# Board.net
KiCad netlist of a schematic drawn in Altium Designer
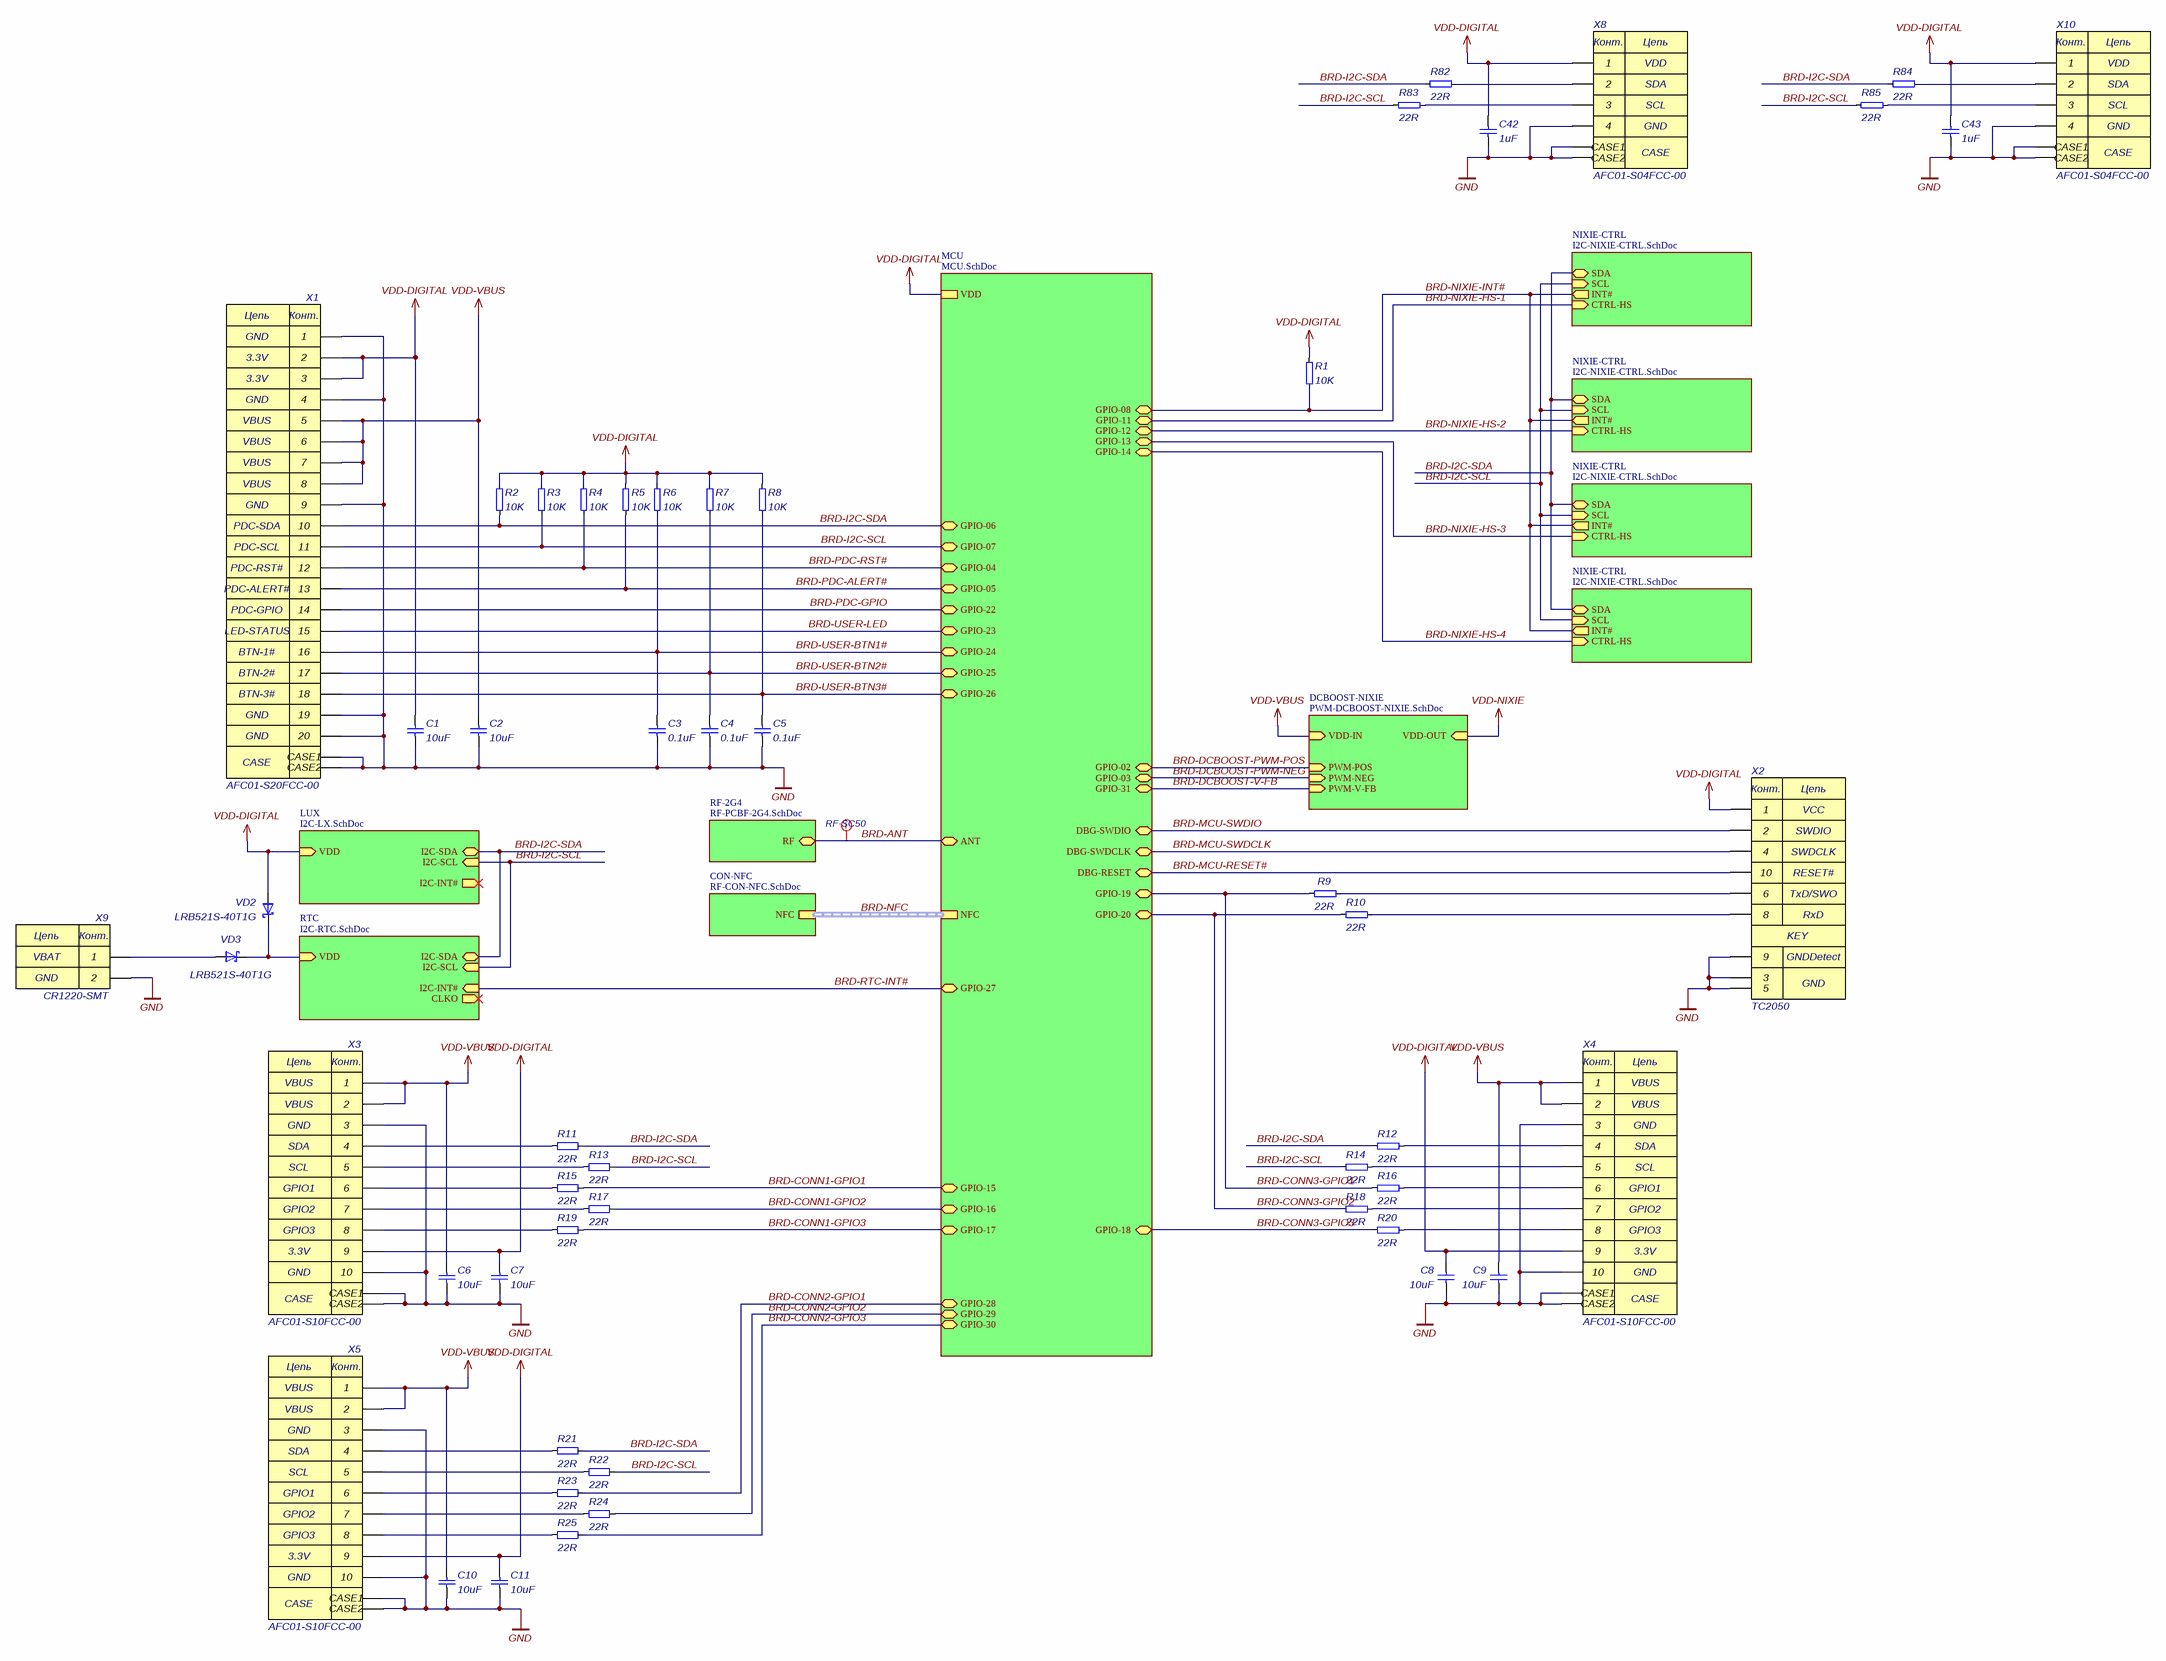
[diagram p0: Board.SchDoc]

(export (version "E")
  (design (tool "Eeschema 10.0.6"))
  (components
    (comp (ref "C1")
      (value "10uF")
      (footprint "C0805")
      (fields
        (field (name "PART NUMBER") "0805-X5R-25V-10uF±10%")
        (field (name "VOLTAGE") "25V")
        (field (name "TOLERANCE") "10%")
      )
      (libsource (lib "ATB") (part "C"))
    )
    (comp (ref "C2")
      (value "10uF")
      (footprint "C0805")
      (fields
        (field (name "PART NUMBER") "0805-X5R-25V-10uF±10%")
        (field (name "VOLTAGE") "25V")
        (field (name "TOLERANCE") "10%")
      )
      (libsource (lib "ATB") (part "C"))
    )
    (comp (ref "C3")
      (value "0.1uF")
      (footprint "C0402")
      (fields
        (field (name "PART NUMBER") "0402-X5R-50V-0.1uF±10%")
        (field (name "VOLTAGE") "50V")
        (field (name "TOLERANCE") "10%")
      )
      (libsource (lib "ATB") (part "C"))
    )
    (comp (ref "C4")
      (value "0.1uF")
      (footprint "C0402")
      (fields
        (field (name "PART NUMBER") "0402-X5R-50V-0.1uF±10%")
        (field (name "VOLTAGE") "50V")
        (field (name "TOLERANCE") "10%")
      )
      (libsource (lib "ATB") (part "C"))
    )
    (comp (ref "C5")
      (value "0.1uF")
      (footprint "C0402")
      (fields
        (field (name "PART NUMBER") "0402-X5R-50V-0.1uF±10%")
        (field (name "VOLTAGE") "50V")
        (field (name "TOLERANCE") "10%")
      )
      (libsource (lib "ATB") (part "C"))
    )
    (comp (ref "C6")
      (value "10uF")
      (footprint "C0805")
      (fields
        (field (name "PART NUMBER") "0805-X5R-25V-10uF±10%")
        (field (name "VOLTAGE") "25V")
        (field (name "TOLERANCE") "10%")
      )
      (libsource (lib "ATB") (part "C"))
    )
    (comp (ref "C7")
      (value "10uF")
      (footprint "C0805")
      (fields
        (field (name "PART NUMBER") "0805-X5R-25V-10uF±10%")
        (field (name "VOLTAGE") "25V")
        (field (name "TOLERANCE") "10%")
      )
      (libsource (lib "ATB") (part "C"))
    )
    (comp (ref "C8")
      (value "10uF")
      (footprint "C0805")
      (fields
        (field (name "PART NUMBER") "0805-X5R-25V-10uF±10%")
        (field (name "VOLTAGE") "25V")
        (field (name "TOLERANCE") "10%")
      )
      (libsource (lib "ATB") (part "C"))
    )
    (comp (ref "C9")
      (value "10uF")
      (footprint "C0805")
      (fields
        (field (name "PART NUMBER") "0805-X5R-25V-10uF±10%")
        (field (name "VOLTAGE") "25V")
        (field (name "TOLERANCE") "10%")
      )
      (libsource (lib "ATB") (part "C"))
    )
    (comp (ref "C10")
      (value "10uF")
      (footprint "C0805")
      (fields
        (field (name "PART NUMBER") "0805-X5R-25V-10uF±10%")
        (field (name "VOLTAGE") "25V")
        (field (name "TOLERANCE") "10%")
      )
      (libsource (lib "ATB") (part "C"))
    )
    (comp (ref "C11")
      (value "10uF")
      (footprint "C0805")
      (fields
        (field (name "PART NUMBER") "0805-X5R-25V-10uF±10%")
        (field (name "VOLTAGE") "25V")
        (field (name "TOLERANCE") "10%")
      )
      (libsource (lib "ATB") (part "C"))
    )
    (comp (ref "C42")
      (value "1uF")
      (footprint "C0402")
      (fields
        (field (name "PART NUMBER") "0402-X5R-10V-01uF±10%")
        (field (name "VOLTAGE") "10V")
        (field (name "TOLERANCE") "10%")
      )
      (libsource (lib "ATB") (part "C"))
    )
    (comp (ref "C43")
      (value "1uF")
      (footprint "C0402")
      (fields
        (field (name "PART NUMBER") "0402-X5R-10V-01uF±10%")
        (field (name "VOLTAGE") "10V")
        (field (name "TOLERANCE") "10%")
      )
      (libsource (lib "ATB") (part "C"))
    )
    (comp (ref "R1")
      (value "10K")
      (footprint "R_0402")
      (fields
        (field (name "PART NUMBER") "0402-0.0625W-10K-100ppm±1%")
        (field (name "TOLERANCE") "1%")
        (field (name "MANUFACTURER") "Yageo")
      )
      (libsource (lib "ATB") (part "R"))
    )
    (comp (ref "R2")
      (value "10K")
      (footprint "R_0402")
      (fields
        (field (name "PART NUMBER") "0402-0.0625W-10K-100ppm±1%")
        (field (name "TOLERANCE") "1%")
        (field (name "MANUFACTURER") "Yageo")
      )
      (libsource (lib "ATB") (part "R"))
    )
    (comp (ref "R3")
      (value "10K")
      (footprint "R_0402")
      (fields
        (field (name "PART NUMBER") "0402-0.0625W-10K-100ppm±1%")
        (field (name "TOLERANCE") "1%")
        (field (name "MANUFACTURER") "Yageo")
      )
      (libsource (lib "ATB") (part "R"))
    )
    (comp (ref "R4")
      (value "10K")
      (footprint "R_0402")
      (fields
        (field (name "PART NUMBER") "0402-0.0625W-10K-100ppm±1%")
        (field (name "TOLERANCE") "1%")
        (field (name "MANUFACTURER") "Yageo")
      )
      (libsource (lib "ATB") (part "R"))
    )
    (comp (ref "R5")
      (value "10K")
      (footprint "R_0402")
      (fields
        (field (name "PART NUMBER") "0402-0.0625W-10K-100ppm±1%")
        (field (name "TOLERANCE") "1%")
        (field (name "MANUFACTURER") "Yageo")
      )
      (libsource (lib "ATB") (part "R"))
    )
    (comp (ref "R6")
      (value "10K")
      (footprint "R_0402")
      (fields
        (field (name "PART NUMBER") "0402-0.0625W-10K-100ppm±1%")
        (field (name "TOLERANCE") "1%")
        (field (name "MANUFACTURER") "Yageo")
      )
      (libsource (lib "ATB") (part "R"))
    )
    (comp (ref "R7")
      (value "10K")
      (footprint "R_0402")
      (fields
        (field (name "PART NUMBER") "0402-0.0625W-10K-100ppm±1%")
        (field (name "TOLERANCE") "1%")
        (field (name "MANUFACTURER") "Yageo")
      )
      (libsource (lib "ATB") (part "R"))
    )
    (comp (ref "R8")
      (value "10K")
      (footprint "R_0402")
      (fields
        (field (name "PART NUMBER") "0402-0.0625W-10K-100ppm±1%")
        (field (name "TOLERANCE") "1%")
        (field (name "MANUFACTURER") "Yageo")
      )
      (libsource (lib "ATB") (part "R"))
    )
    (comp (ref "R9")
      (value "22R")
      (footprint "R_0402")
      (fields
        (field (name "PART NUMBER") "0402-0.0625W-22R-100ppm±1%")
        (field (name "TOLERANCE") "1%")
        (field (name "MANUFACTURER") "Yageo")
      )
      (libsource (lib "ATB") (part "R"))
    )
    (comp (ref "R10")
      (value "22R")
      (footprint "R_0402")
      (fields
        (field (name "PART NUMBER") "0402-0.0625W-22R-100ppm±1%")
        (field (name "TOLERANCE") "1%")
        (field (name "MANUFACTURER") "Yageo")
      )
      (libsource (lib "ATB") (part "R"))
    )
    (comp (ref "R11")
      (value "22R")
      (footprint "R_0402")
      (fields
        (field (name "PART NUMBER") "0402-0.0625W-22R-100ppm±1%")
        (field (name "TOLERANCE") "1%")
        (field (name "MANUFACTURER") "Yageo")
      )
      (libsource (lib "ATB") (part "R"))
    )
    (comp (ref "R12")
      (value "22R")
      (footprint "R_0402")
      (fields
        (field (name "PART NUMBER") "0402-0.0625W-22R-100ppm±1%")
        (field (name "TOLERANCE") "1%")
        (field (name "MANUFACTURER") "Yageo")
      )
      (libsource (lib "ATB") (part "R"))
    )
    (comp (ref "R13")
      (value "22R")
      (footprint "R_0402")
      (fields
        (field (name "PART NUMBER") "0402-0.0625W-22R-100ppm±1%")
        (field (name "TOLERANCE") "1%")
        (field (name "MANUFACTURER") "Yageo")
      )
      (libsource (lib "ATB") (part "R"))
    )
    (comp (ref "R14")
      (value "22R")
      (footprint "R_0402")
      (fields
        (field (name "PART NUMBER") "0402-0.0625W-22R-100ppm±1%")
        (field (name "TOLERANCE") "1%")
        (field (name "MANUFACTURER") "Yageo")
      )
      (libsource (lib "ATB") (part "R"))
    )
    (comp (ref "R15")
      (value "22R")
      (footprint "R_0402")
      (fields
        (field (name "PART NUMBER") "0402-0.0625W-22R-100ppm±1%")
        (field (name "TOLERANCE") "1%")
        (field (name "MANUFACTURER") "Yageo")
      )
      (libsource (lib "ATB") (part "R"))
    )
    (comp (ref "R16")
      (value "22R")
      (footprint "R_0402")
      (fields
        (field (name "PART NUMBER") "0402-0.0625W-22R-100ppm±1%")
        (field (name "TOLERANCE") "1%")
        (field (name "MANUFACTURER") "Yageo")
      )
      (libsource (lib "ATB") (part "R"))
    )
    (comp (ref "R17")
      (value "22R")
      (footprint "R_0402")
      (fields
        (field (name "PART NUMBER") "0402-0.0625W-22R-100ppm±1%")
        (field (name "TOLERANCE") "1%")
        (field (name "MANUFACTURER") "Yageo")
      )
      (libsource (lib "ATB") (part "R"))
    )
    (comp (ref "R18")
      (value "22R")
      (footprint "R_0402")
      (fields
        (field (name "PART NUMBER") "0402-0.0625W-22R-100ppm±1%")
        (field (name "TOLERANCE") "1%")
        (field (name "MANUFACTURER") "Yageo")
      )
      (libsource (lib "ATB") (part "R"))
    )
    (comp (ref "R19")
      (value "22R")
      (footprint "R_0402")
      (fields
        (field (name "PART NUMBER") "0402-0.0625W-22R-100ppm±1%")
        (field (name "TOLERANCE") "1%")
        (field (name "MANUFACTURER") "Yageo")
      )
      (libsource (lib "ATB") (part "R"))
    )
    (comp (ref "R20")
      (value "22R")
      (footprint "R_0402")
      (fields
        (field (name "PART NUMBER") "0402-0.0625W-22R-100ppm±1%")
        (field (name "TOLERANCE") "1%")
        (field (name "MANUFACTURER") "Yageo")
      )
      (libsource (lib "ATB") (part "R"))
    )
    (comp (ref "R21")
      (value "22R")
      (footprint "R_0402")
      (fields
        (field (name "PART NUMBER") "0402-0.0625W-22R-100ppm±1%")
        (field (name "TOLERANCE") "1%")
        (field (name "MANUFACTURER") "Yageo")
      )
      (libsource (lib "ATB") (part "R"))
    )
    (comp (ref "R22")
      (value "22R")
      (footprint "R_0402")
      (fields
        (field (name "PART NUMBER") "0402-0.0625W-22R-100ppm±1%")
        (field (name "TOLERANCE") "1%")
        (field (name "MANUFACTURER") "Yageo")
      )
      (libsource (lib "ATB") (part "R"))
    )
    (comp (ref "R23")
      (value "22R")
      (footprint "R_0402")
      (fields
        (field (name "PART NUMBER") "0402-0.0625W-22R-100ppm±1%")
        (field (name "TOLERANCE") "1%")
        (field (name "MANUFACTURER") "Yageo")
      )
      (libsource (lib "ATB") (part "R"))
    )
    (comp (ref "R24")
      (value "22R")
      (footprint "R_0402")
      (fields
        (field (name "PART NUMBER") "0402-0.0625W-22R-100ppm±1%")
        (field (name "TOLERANCE") "1%")
        (field (name "MANUFACTURER") "Yageo")
      )
      (libsource (lib "ATB") (part "R"))
    )
    (comp (ref "R25")
      (value "22R")
      (footprint "R_0402")
      (fields
        (field (name "PART NUMBER") "0402-0.0625W-22R-100ppm±1%")
        (field (name "TOLERANCE") "1%")
        (field (name "MANUFACTURER") "Yageo")
      )
      (libsource (lib "ATB") (part "R"))
    )
    (comp (ref "R82")
      (value "22R")
      (footprint "R_0402")
      (fields
        (field (name "PART NUMBER") "0402-0.0625W-22R-100ppm±1%")
        (field (name "TOLERANCE") "1%")
        (field (name "MANUFACTURER") "Yageo")
      )
      (libsource (lib "ATB") (part "R"))
    )
    (comp (ref "R83")
      (value "22R")
      (footprint "R_0402")
      (fields
        (field (name "PART NUMBER") "0402-0.0625W-22R-100ppm±1%")
        (field (name "TOLERANCE") "1%")
        (field (name "MANUFACTURER") "Yageo")
      )
      (libsource (lib "ATB") (part "R"))
    )
    (comp (ref "R84")
      (value "22R")
      (footprint "R_0402")
      (fields
        (field (name "PART NUMBER") "0402-0.0625W-22R-100ppm±1%")
        (field (name "TOLERANCE") "1%")
        (field (name "MANUFACTURER") "Yageo")
      )
      (libsource (lib "ATB") (part "R"))
    )
    (comp (ref "R85")
      (value "22R")
      (footprint "R_0402")
      (fields
        (field (name "PART NUMBER") "0402-0.0625W-22R-100ppm±1%")
        (field (name "TOLERANCE") "1%")
        (field (name "MANUFACTURER") "Yageo")
      )
      (libsource (lib "ATB") (part "R"))
    )
    (comp (ref "VD2")
      (value "LRB521S-40T1G")
      (footprint "SOD-523")
      (description "40V 300mV 200mA SOD-523 Schottky Barrier Diode")
      (fields (field (name "MANUFACTURER") "LRC"))
      (libsource (lib "ATB") (part "Shotki"))
    )
    (comp (ref "VD3")
      (value "LRB521S-40T1G")
      (footprint "SOD-523")
      (description "40V 300mV 200mA SOD-523 Schottky Barrier Diode")
      (fields (field (name "MANUFACTURER") "LRC"))
      (libsource (lib "ATB") (part "Shotki"))
    )
    (comp (ref "X1")
      (value "AFC01-S20FCC-00")
      (footprint "505110-2096")
      (description "Clamshell -25℃~+85℃ 20P Bottom Contact Surface Mount，Right Angle 0.5mm FFC/FPC Connector")
      (fields (field (name "MANUFACTURER") "JUSHUO"))
      (libsource (lib "ATB") (part "H20+2xCase"))
    )
    (comp (ref "X2")
      (value "TC2050")
      (footprint "TC2050-IDC-FP")
      (description "TAG Connect 10 pin ARM swd compatilbe with UART")
      (fields (field (name "PART NUMBER") "PCB-TAGC-10PIN-SWD-UART"))
      (libsource (lib "ATB") (part "PCB-TAGC-10PIN-SWD-UART"))
    )
    (comp (ref "X3")
      (value "AFC01-S10FCC-00")
      (footprint "505110-1096")
      (description "Clamshell -25℃~+85℃ 10P Bottom Contact Surface Mount，Right Angle 0.5mm FFC/FPC Connector")
      (fields (field (name "MANUFACTURER") "JUSHUO"))
      (libsource (lib "ATB") (part "H10+2xCase"))
    )
    (comp (ref "X4")
      (value "AFC01-S10FCC-00")
      (footprint "505110-1096")
      (description "Clamshell -25℃~+85℃ 10P Bottom Contact Surface Mount，Right Angle 0.5mm FFC/FPC Connector")
      (fields (field (name "MANUFACTURER") "JUSHUO"))
      (libsource (lib "") (part "H10+2xCase_1"))
    )
    (comp (ref "X5")
      (value "AFC01-S10FCC-00")
      (footprint "505110-1096")
      (description "Clamshell -25℃~+85℃ 10P Bottom Contact Surface Mount，Right Angle 0.5mm FFC/FPC Connector")
      (fields (field (name "MANUFACTURER") "JUSHUO"))
      (libsource (lib "ATB") (part "H10+2xCase"))
    )
    (comp (ref "X8")
      (value "AFC01-S04FCC-00")
      (footprint "505110-0492")
      (description "Clamshell 4P Bottom Contact Surface Mount, Right Angle 0.5mm, FFC/FPC Connector")
      (fields (field (name "MANUFACTURER") "JUSHUO"))
      (libsource (lib "ATB") (part "H4+2xCase"))
    )
    (comp (ref "X9")
      (value "CR1220-SMT")
      (footprint "BAT-HLDR-CR1220-SMT")
      (description "Battery base -25℃~+85℃ CR1220 SMD Battery Connector")
      (fields (field (name "PART NUMBER") "L-KLS5-CR1220-02"))
      (libsource (lib "ATB") (part "H2"))
    )
    (comp (ref "X10")
      (value "AFC01-S04FCC-00")
      (footprint "505110-0492")
      (description "Clamshell 4P Bottom Contact Surface Mount, Right Angle 0.5mm, FFC/FPC Connector")
      (fields (field (name "MANUFACTURER") "JUSHUO"))
      (libsource (lib "ATB") (part "H4+2xCase"))
    )
  )
  (nets
    (net (code "3") (name "/BRD-CONN1-GPIO1") (class "Default")
      (node (ref "R15") (pin "2") (pinfunction "2_2") (pintype "passive"))
    )
    (net (code "4") (name "/BRD-CONN1-GPIO2") (class "Default")
      (node (ref "R17") (pin "2") (pinfunction "2_2") (pintype "passive"))
    )
    (net (code "5") (name "/BRD-CONN1-GPIO3") (class "Default")
      (node (ref "R19") (pin "2") (pinfunction "2_2") (pintype "passive"))
    )
    (net (code "6") (name "/BRD-CONN2-GPIO1") (class "Default")
      (node (ref "R23") (pin "2") (pinfunction "2_2") (pintype "passive"))
    )
    (net (code "7") (name "/BRD-CONN2-GPIO2") (class "Default")
      (node (ref "R24") (pin "2") (pinfunction "2_2") (pintype "passive"))
    )
    (net (code "8") (name "/BRD-CONN2-GPIO3") (class "Default")
      (node (ref "R25") (pin "2") (pinfunction "2_2") (pintype "passive"))
    )
    (net (code "9") (name "/BRD-CONN3-GPIO1") (class "Default")
      (node (ref "R16") (pin "2") (pinfunction "2_2") (pintype "passive"))
      (node (ref "R9") (pin "2") (pinfunction "2_2") (pintype "passive"))
    )
    (net (code "10") (name "/BRD-CONN3-GPIO2") (class "Default")
      (node (ref "R10") (pin "2") (pinfunction "2_2") (pintype "passive"))
      (node (ref "R18") (pin "2") (pinfunction "2_2") (pintype "passive"))
    )
    (net (code "11") (name "/BRD-CONN3-GPIO3") (class "Default")
      (node (ref "R20") (pin "2") (pinfunction "2_2") (pintype "passive"))
    )
    (net (code "15") (name "/BRD-I2C-SCL") (class "Default")
      (node (ref "R13") (pin "2") (pinfunction "2_2") (pintype "passive"))
      (node (ref "R14") (pin "2") (pinfunction "2_2") (pintype "passive"))
      (node (ref "R22") (pin "2") (pinfunction "2_2") (pintype "passive"))
      (node (ref "R3") (pin "2") (pinfunction "2_2") (pintype "passive"))
      (node (ref "R83") (pin "2") (pinfunction "2_2") (pintype "passive"))
      (node (ref "R85") (pin "2") (pinfunction "2_2") (pintype "passive"))
      (node (ref "X1") (pin "11") (pinfunction "11_11") (pintype "passive"))
    )
    (net (code "16") (name "/BRD-I2C-SDA") (class "Default")
      (node (ref "R11") (pin "2") (pinfunction "2_2") (pintype "passive"))
      (node (ref "R12") (pin "2") (pinfunction "2_2") (pintype "passive"))
      (node (ref "R2") (pin "2") (pinfunction "2_2") (pintype "passive"))
      (node (ref "R21") (pin "2") (pinfunction "2_2") (pintype "passive"))
      (node (ref "R82") (pin "2") (pinfunction "2_2") (pintype "passive"))
      (node (ref "R84") (pin "2") (pinfunction "2_2") (pintype "passive"))
      (node (ref "X1") (pin "10") (pinfunction "10_10") (pintype "passive"))
    )
    (net (code "17") (name "/BRD-MCU-RESET#") (class "Default")
      (node (ref "X2") (pin "10") (pinfunction "10_10") (pintype "passive"))
    )
    (net (code "18") (name "/BRD-MCU-SWDCLK") (class "Default")
      (node (ref "X2") (pin "4") (pinfunction "4_4") (pintype "passive"))
    )
    (net (code "19") (name "/BRD-MCU-SWDIO") (class "Default")
      (node (ref "X2") (pin "2") (pinfunction "2_2") (pintype "passive"))
    )
    (net (code "24") (name "/BRD-NIXIE-INT#") (class "Default")
      (node (ref "R1") (pin "2") (pinfunction "2_2") (pintype "passive"))
    )
    (net (code "25") (name "/BRD-PDC-ALERT#") (class "Default")
      (node (ref "R5") (pin "2") (pinfunction "2_2") (pintype "passive"))
      (node (ref "X1") (pin "13") (pinfunction "13_13") (pintype "passive"))
    )
    (net (code "26") (name "/BRD-PDC-GPIO") (class "Default")
      (node (ref "X1") (pin "14") (pinfunction "14_14") (pintype "passive"))
    )
    (net (code "27") (name "/BRD-PDC-RST#") (class "Default")
      (node (ref "R4") (pin "2") (pinfunction "2_2") (pintype "passive"))
      (node (ref "X1") (pin "12") (pinfunction "12_12") (pintype "passive"))
    )
    (net (code "29") (name "/BRD-USER-BTN1#") (class "Default")
      (node (ref "C3") (pin "2") (pinfunction "2_2") (pintype "passive"))
      (node (ref "R6") (pin "2") (pinfunction "2_2") (pintype "passive"))
      (node (ref "X1") (pin "16") (pinfunction "16_16") (pintype "passive"))
    )
    (net (code "30") (name "/BRD-USER-BTN2#") (class "Default")
      (node (ref "C4") (pin "2") (pinfunction "2_2") (pintype "passive"))
      (node (ref "R7") (pin "2") (pinfunction "2_2") (pintype "passive"))
      (node (ref "X1") (pin "17") (pinfunction "17_17") (pintype "passive"))
    )
    (net (code "31") (name "/BRD-USER-BTN3#") (class "Default")
      (node (ref "C5") (pin "2") (pinfunction "2_2") (pintype "passive"))
      (node (ref "R8") (pin "2") (pinfunction "2_2") (pintype "passive"))
      (node (ref "X1") (pin "18") (pinfunction "18_18") (pintype "passive"))
    )
    (net (code "32") (name "/BRD-USER-LED") (class "Default")
      (node (ref "X1") (pin "15") (pinfunction "15_15") (pintype "passive"))
    )
    (net (code "35") (name "/VDD") (class "Default")
      (node (ref "VD2") (pin "1") (pinfunction "K_1") (pintype "passive"))
      (node (ref "VD3") (pin "1") (pinfunction "K_1") (pintype "passive"))
    )
    (net (code "37") (name "GND") (class "Default")
      (node (ref "C1") (pin "2") (pinfunction "2_2") (pintype "passive"))
      (node (ref "C10") (pin "2") (pinfunction "2_2") (pintype "passive"))
      (node (ref "C11") (pin "2") (pinfunction "2_2") (pintype "passive"))
      (node (ref "C2") (pin "2") (pinfunction "2_2") (pintype "passive"))
      (node (ref "C3") (pin "1") (pinfunction "1_1") (pintype "passive"))
      (node (ref "C4") (pin "1") (pinfunction "1_1") (pintype "passive"))
      (node (ref "C42") (pin "1") (pinfunction "1_1") (pintype "passive"))
      (node (ref "C43") (pin "1") (pinfunction "1_1") (pintype "passive"))
      (node (ref "C5") (pin "1") (pinfunction "1_1") (pintype "passive"))
      (node (ref "C6") (pin "2") (pinfunction "2_2") (pintype "passive"))
      (node (ref "C7") (pin "2") (pinfunction "2_2") (pintype "passive"))
      (node (ref "C8") (pin "2") (pinfunction "2_2") (pintype "passive"))
      (node (ref "C9") (pin "2") (pinfunction "2_2") (pintype "passive"))
      (node (ref "X1") (pin "1") (pinfunction "1_1") (pintype "passive"))
      (node (ref "X1") (pin "19") (pinfunction "19_19") (pintype "passive"))
      (node (ref "X1") (pin "20") (pinfunction "20_20") (pintype "passive"))
      (node (ref "X1") (pin "4") (pinfunction "4_4") (pintype "passive"))
      (node (ref "X1") (pin "9") (pinfunction "9_9") (pintype "passive"))
      (node (ref "X1") (pin "CASE1") (pinfunction "CASE1_CASE1") (pintype "passive"))
      (node (ref "X1") (pin "CASE2") (pinfunction "CASE2_CASE2") (pintype "passive"))
      (node (ref "X10") (pin "4") (pinfunction "4_4") (pintype "passive"))
      (node (ref "X10") (pin "CASE1") (pinfunction "CASE1_CASE1") (pintype "passive"))
      (node (ref "X10") (pin "CASE2") (pinfunction "CASE2_CASE2") (pintype "passive"))
      (node (ref "X2") (pin "3") (pinfunction "3_3") (pintype "passive"))
      (node (ref "X2") (pin "5") (pinfunction "5_5") (pintype "passive"))
      (node (ref "X2") (pin "9") (pinfunction "9_9") (pintype "passive"))
      (node (ref "X3") (pin "10") (pinfunction "10_10") (pintype "passive"))
      (node (ref "X3") (pin "3") (pinfunction "3_3") (pintype "passive"))
      (node (ref "X3") (pin "CASE1") (pinfunction "CASE1_CASE1") (pintype "passive"))
      (node (ref "X3") (pin "CASE2") (pinfunction "CASE2_CASE2") (pintype "passive"))
      (node (ref "X4") (pin "10") (pinfunction "10_10") (pintype "passive"))
      (node (ref "X4") (pin "3") (pinfunction "3_3") (pintype "passive"))
      (node (ref "X4") (pin "CASE1") (pinfunction "CASE1_CASE1") (pintype "passive"))
      (node (ref "X4") (pin "CASE2") (pinfunction "CASE2_CASE2") (pintype "passive"))
      (node (ref "X5") (pin "10") (pinfunction "10_10") (pintype "passive"))
      (node (ref "X5") (pin "3") (pinfunction "3_3") (pintype "passive"))
      (node (ref "X5") (pin "CASE1") (pinfunction "CASE1_CASE1") (pintype "passive"))
      (node (ref "X5") (pin "CASE2") (pinfunction "CASE2_CASE2") (pintype "passive"))
      (node (ref "X8") (pin "4") (pinfunction "4_4") (pintype "passive"))
      (node (ref "X8") (pin "CASE1") (pinfunction "CASE1_CASE1") (pintype "passive"))
      (node (ref "X8") (pin "CASE2") (pinfunction "CASE2_CASE2") (pintype "passive"))
      (node (ref "X9") (pin "2") (pinfunction "2_2") (pintype "passive"))
    )
    (net (code "38") (name "Net-(R9-Pad1)") (class "Default")
      (node (ref "R9") (pin "1") (pinfunction "1_1") (pintype "passive"))
      (node (ref "X2") (pin "6") (pinfunction "6_6") (pintype "passive"))
    )
    (net (code "39") (name "Net-(R10-Pad1)") (class "Default")
      (node (ref "R10") (pin "1") (pinfunction "1_1") (pintype "passive"))
      (node (ref "X2") (pin "8") (pinfunction "8_8") (pintype "passive"))
    )
    (net (code "40") (name "Net-(R11-Pad1)") (class "Default")
      (node (ref "R11") (pin "1") (pinfunction "1_1") (pintype "passive"))
      (node (ref "X3") (pin "4") (pinfunction "4_4") (pintype "passive"))
    )
    (net (code "41") (name "Net-(R12-Pad1)") (class "Default")
      (node (ref "R12") (pin "1") (pinfunction "1_1") (pintype "passive"))
      (node (ref "X4") (pin "4") (pinfunction "4_4") (pintype "passive"))
    )
    (net (code "42") (name "Net-(R13-Pad1)") (class "Default")
      (node (ref "R13") (pin "1") (pinfunction "1_1") (pintype "passive"))
      (node (ref "X3") (pin "5") (pinfunction "5_5") (pintype "passive"))
    )
    (net (code "43") (name "Net-(R14-Pad1)") (class "Default")
      (node (ref "R14") (pin "1") (pinfunction "1_1") (pintype "passive"))
      (node (ref "X4") (pin "5") (pinfunction "5_5") (pintype "passive"))
    )
    (net (code "44") (name "Net-(R15-Pad1)") (class "Default")
      (node (ref "R15") (pin "1") (pinfunction "1_1") (pintype "passive"))
      (node (ref "X3") (pin "6") (pinfunction "6_6") (pintype "passive"))
    )
    (net (code "45") (name "Net-(R16-Pad1)") (class "Default")
      (node (ref "R16") (pin "1") (pinfunction "1_1") (pintype "passive"))
      (node (ref "X4") (pin "6") (pinfunction "6_6") (pintype "passive"))
    )
    (net (code "46") (name "Net-(R17-Pad1)") (class "Default")
      (node (ref "R17") (pin "1") (pinfunction "1_1") (pintype "passive"))
      (node (ref "X3") (pin "7") (pinfunction "7_7") (pintype "passive"))
    )
    (net (code "47") (name "Net-(R18-Pad1)") (class "Default")
      (node (ref "R18") (pin "1") (pinfunction "1_1") (pintype "passive"))
      (node (ref "X4") (pin "7") (pinfunction "7_7") (pintype "passive"))
    )
    (net (code "48") (name "Net-(R19-Pad1)") (class "Default")
      (node (ref "R19") (pin "1") (pinfunction "1_1") (pintype "passive"))
      (node (ref "X3") (pin "8") (pinfunction "8_8") (pintype "passive"))
    )
    (net (code "49") (name "Net-(R20-Pad1)") (class "Default")
      (node (ref "R20") (pin "1") (pinfunction "1_1") (pintype "passive"))
      (node (ref "X4") (pin "8") (pinfunction "8_8") (pintype "passive"))
    )
    (net (code "50") (name "Net-(R21-Pad1)") (class "Default")
      (node (ref "R21") (pin "1") (pinfunction "1_1") (pintype "passive"))
      (node (ref "X5") (pin "4") (pinfunction "4_4") (pintype "passive"))
    )
    (net (code "51") (name "Net-(R22-Pad1)") (class "Default")
      (node (ref "R22") (pin "1") (pinfunction "1_1") (pintype "passive"))
      (node (ref "X5") (pin "5") (pinfunction "5_5") (pintype "passive"))
    )
    (net (code "52") (name "Net-(R23-Pad1)") (class "Default")
      (node (ref "R23") (pin "1") (pinfunction "1_1") (pintype "passive"))
      (node (ref "X5") (pin "6") (pinfunction "6_6") (pintype "passive"))
    )
    (net (code "53") (name "Net-(R24-Pad1)") (class "Default")
      (node (ref "R24") (pin "1") (pinfunction "1_1") (pintype "passive"))
      (node (ref "X5") (pin "7") (pinfunction "7_7") (pintype "passive"))
    )
    (net (code "54") (name "Net-(R25-Pad1)") (class "Default")
      (node (ref "R25") (pin "1") (pinfunction "1_1") (pintype "passive"))
      (node (ref "X5") (pin "8") (pinfunction "8_8") (pintype "passive"))
    )
    (net (code "55") (name "Net-(R82-Pad1)") (class "Default")
      (node (ref "R82") (pin "1") (pinfunction "1_1") (pintype "passive"))
      (node (ref "X8") (pin "2") (pinfunction "2_2") (pintype "passive"))
    )
    (net (code "56") (name "Net-(R83-Pad1)") (class "Default")
      (node (ref "R83") (pin "1") (pinfunction "1_1") (pintype "passive"))
      (node (ref "X8") (pin "3") (pinfunction "3_3") (pintype "passive"))
    )
    (net (code "57") (name "Net-(R84-Pad1)") (class "Default")
      (node (ref "R84") (pin "1") (pinfunction "1_1") (pintype "passive"))
      (node (ref "X10") (pin "2") (pinfunction "2_2") (pintype "passive"))
    )
    (net (code "58") (name "Net-(R85-Pad1)") (class "Default")
      (node (ref "R85") (pin "1") (pinfunction "1_1") (pintype "passive"))
      (node (ref "X10") (pin "3") (pinfunction "3_3") (pintype "passive"))
    )
    (net (code "59") (name "Net-(VD3-A)") (class "Default")
      (node (ref "VD3") (pin "2") (pinfunction "A_2") (pintype "passive"))
      (node (ref "X9") (pin "1") (pinfunction "1_1") (pintype "passive"))
    )
    (net (code "60") (name "VDD-DIGITAL") (class "Default")
      (node (ref "C1") (pin "1") (pinfunction "1_1") (pintype "passive"))
      (node (ref "C11") (pin "1") (pinfunction "1_1") (pintype "passive"))
      (node (ref "C42") (pin "2") (pinfunction "2_2") (pintype "passive"))
      (node (ref "C43") (pin "2") (pinfunction "2_2") (pintype "passive"))
      (node (ref "C7") (pin "1") (pinfunction "1_1") (pintype "passive"))
      (node (ref "C8") (pin "1") (pinfunction "1_1") (pintype "passive"))
      (node (ref "R1") (pin "1") (pinfunction "1_1") (pintype "passive"))
      (node (ref "R2") (pin "1") (pinfunction "1_1") (pintype "passive"))
      (node (ref "R3") (pin "1") (pinfunction "1_1") (pintype "passive"))
      (node (ref "R4") (pin "1") (pinfunction "1_1") (pintype "passive"))
      (node (ref "R5") (pin "1") (pinfunction "1_1") (pintype "passive"))
      (node (ref "R6") (pin "1") (pinfunction "1_1") (pintype "passive"))
      (node (ref "R7") (pin "1") (pinfunction "1_1") (pintype "passive"))
      (node (ref "R8") (pin "1") (pinfunction "1_1") (pintype "passive"))
      (node (ref "VD2") (pin "2") (pinfunction "A_2") (pintype "passive"))
      (node (ref "X1") (pin "2") (pinfunction "2_2") (pintype "passive"))
      (node (ref "X1") (pin "3") (pinfunction "3_3") (pintype "passive"))
      (node (ref "X10") (pin "1") (pinfunction "1_1") (pintype "passive"))
      (node (ref "X2") (pin "1") (pinfunction "1_1") (pintype "passive"))
      (node (ref "X3") (pin "9") (pinfunction "9_9") (pintype "passive"))
      (node (ref "X4") (pin "9") (pinfunction "9_9") (pintype "passive"))
      (node (ref "X5") (pin "9") (pinfunction "9_9") (pintype "passive"))
      (node (ref "X8") (pin "1") (pinfunction "1_1") (pintype "passive"))
    )
    (net (code "62") (name "VDD-VBUS") (class "Default")
      (node (ref "C10") (pin "1") (pinfunction "1_1") (pintype "passive"))
      (node (ref "C2") (pin "1") (pinfunction "1_1") (pintype "passive"))
      (node (ref "C6") (pin "1") (pinfunction "1_1") (pintype "passive"))
      (node (ref "C9") (pin "1") (pinfunction "1_1") (pintype "passive"))
      (node (ref "X1") (pin "5") (pinfunction "5_5") (pintype "passive"))
      (node (ref "X1") (pin "6") (pinfunction "6_6") (pintype "passive"))
      (node (ref "X1") (pin "7") (pinfunction "7_7") (pintype "passive"))
      (node (ref "X1") (pin "8") (pinfunction "8_8") (pintype "passive"))
      (node (ref "X3") (pin "1") (pinfunction "1_1") (pintype "passive"))
      (node (ref "X3") (pin "2") (pinfunction "2_2") (pintype "passive"))
      (node (ref "X4") (pin "1") (pinfunction "1_1") (pintype "passive"))
      (node (ref "X4") (pin "2") (pinfunction "2_2") (pintype "passive"))
      (node (ref "X5") (pin "1") (pinfunction "1_1") (pintype "passive"))
      (node (ref "X5") (pin "2") (pinfunction "2_2") (pintype "passive"))
    )
  )
)
